# Power_supplies.net
KiCad netlist of a schematic drawn in Altium Designer
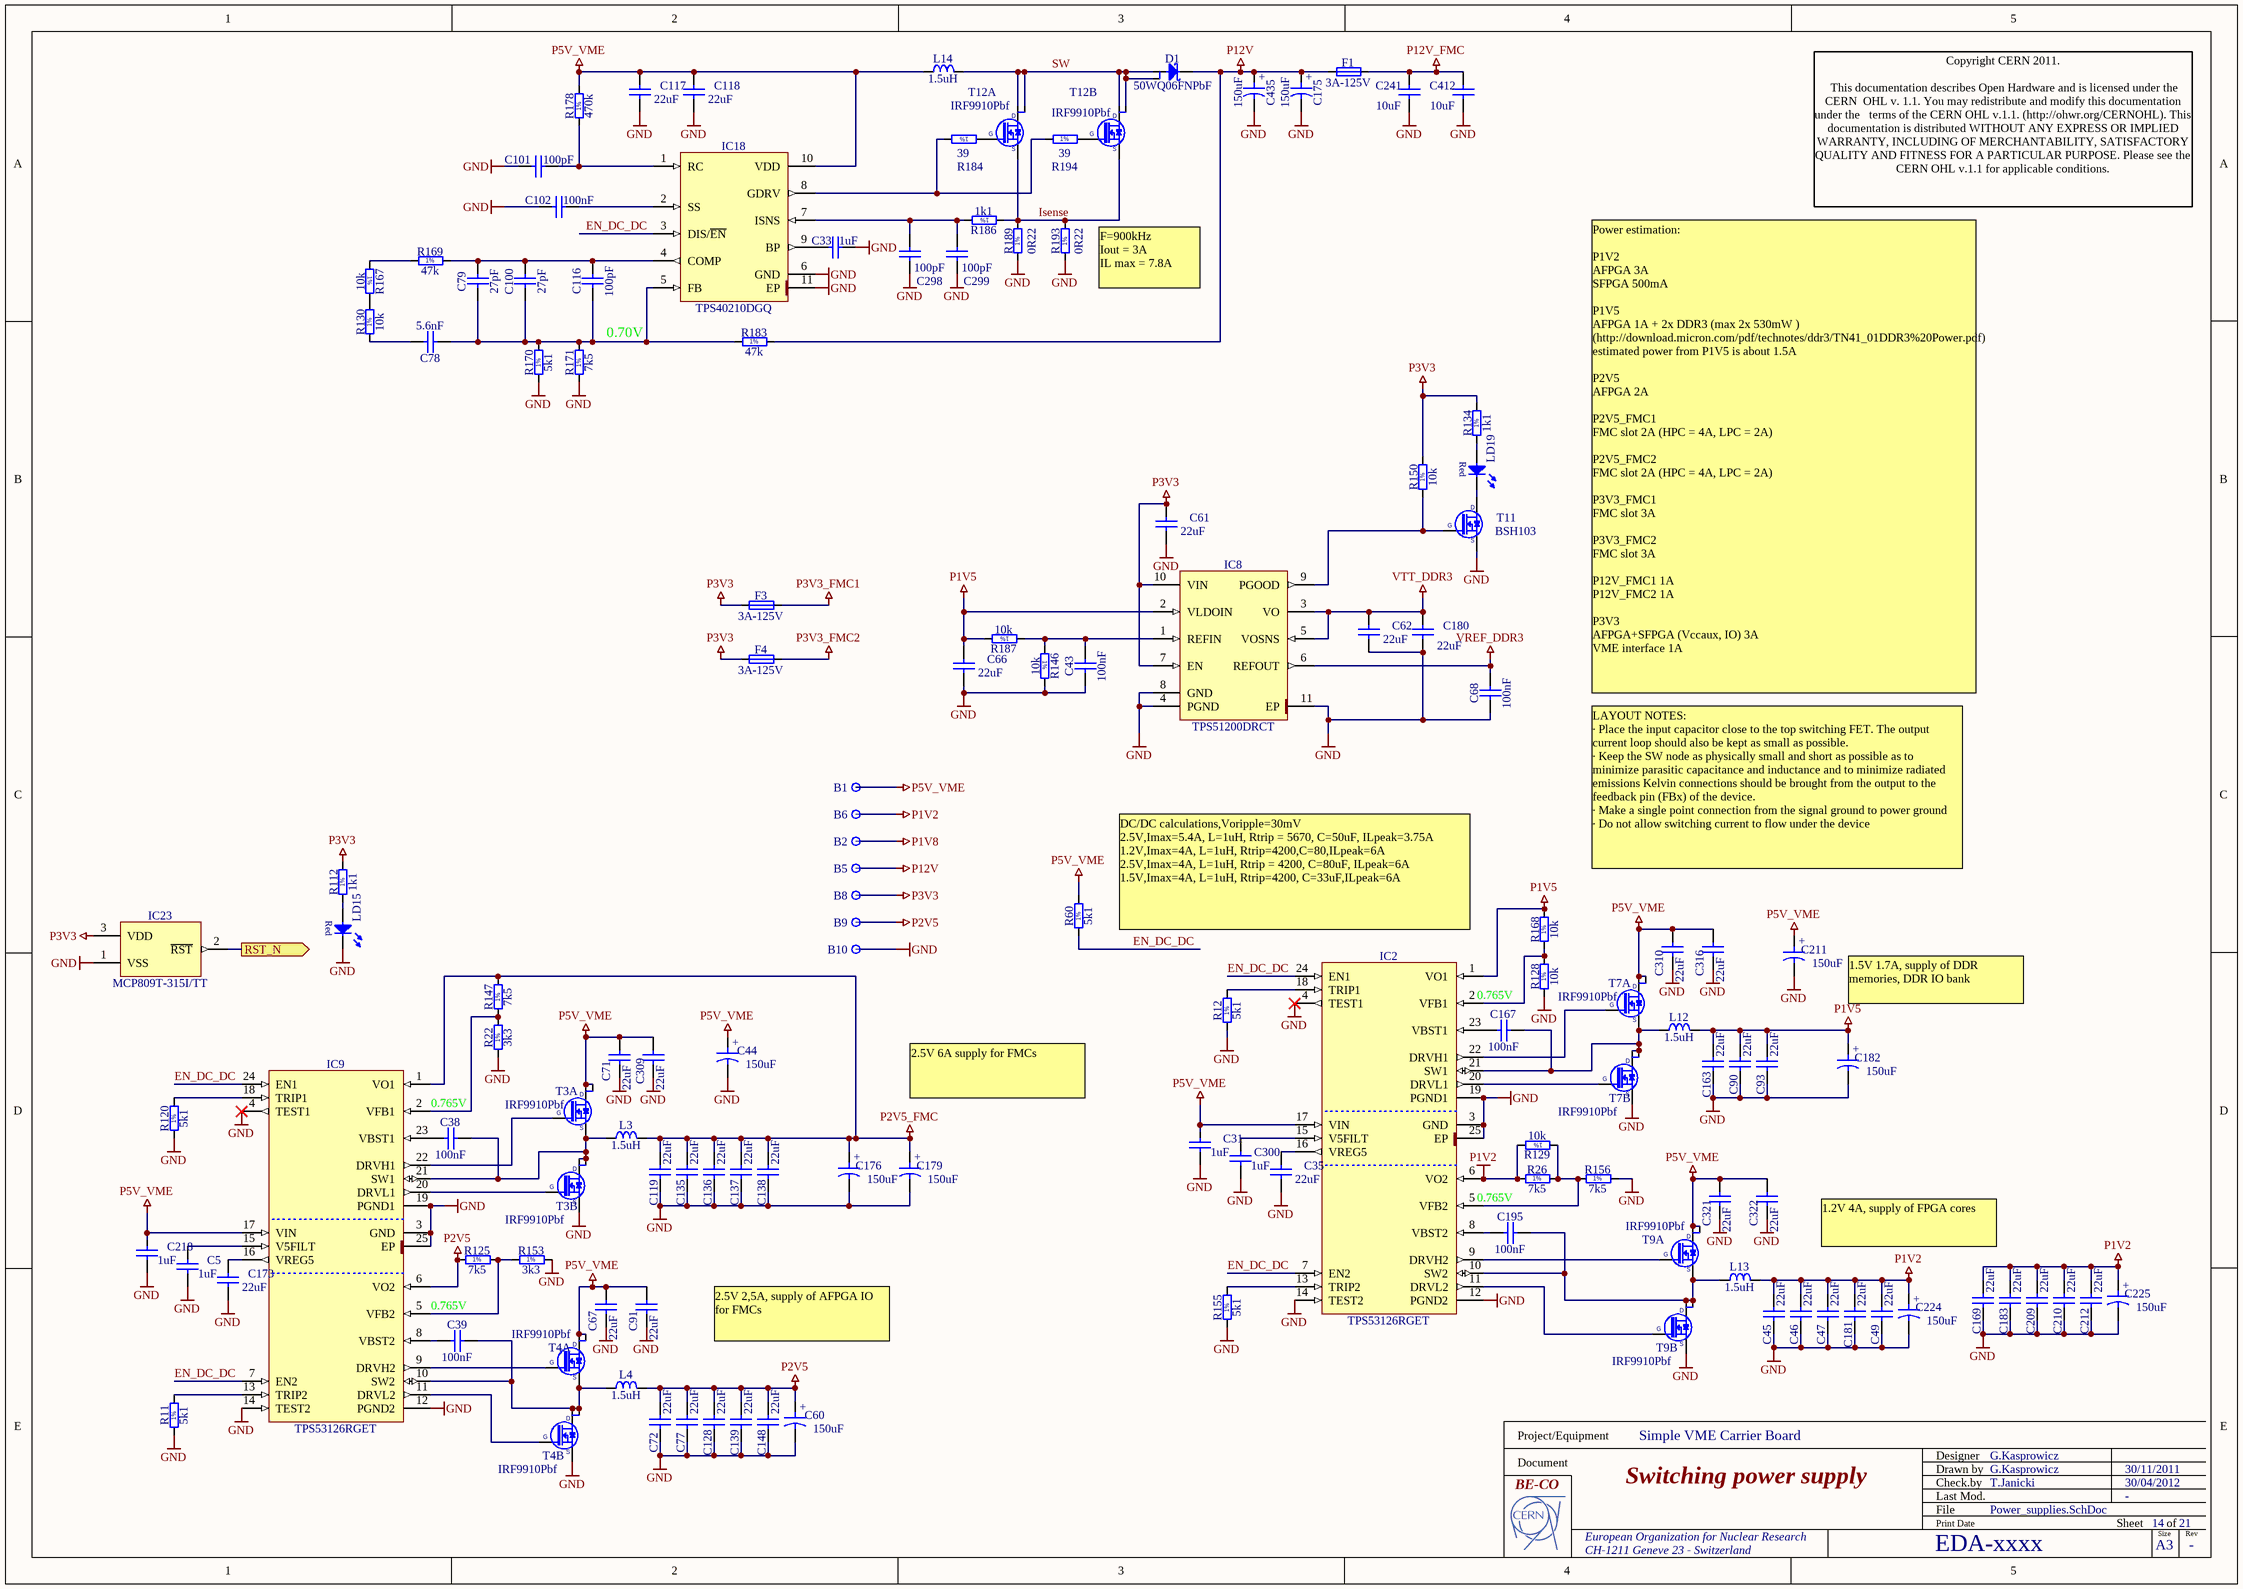
[diagram p0: Power_supplies.SchDoc]

(export (version "E")
  (design (tool "Eeschema 10.0.6"))
  (components
    (comp (ref "B1")
      (value "Plated Hole")
      (footprint "c130h80")
      (description "Single Terminal Socket")
      (fields (field (name "PART NUMBER") "PLATED_HOLE0.8_PAD1.3") (field (name "AUTHOR") "CERN DEM JLC"))
      (libsource (lib "Eletro-mechanical") (part "Single Terminal Socket"))
    )
    (comp (ref "B2")
      (value "Plated Hole")
      (footprint "c130h80")
      (description "Single Terminal Socket")
      (fields (field (name "PART NUMBER") "PLATED_HOLE0.8_PAD1.3") (field (name "AUTHOR") "CERN DEM JLC"))
      (libsource (lib "Eletro-mechanical") (part "Single Terminal Socket"))
    )
    (comp (ref "B5")
      (value "Plated Hole")
      (footprint "c130h80")
      (description "Single Terminal Socket")
      (fields (field (name "PART NUMBER") "PLATED_HOLE0.8_PAD1.3") (field (name "AUTHOR") "CERN DEM JLC"))
      (libsource (lib "Eletro-mechanical") (part "Single Terminal Socket"))
    )
    (comp (ref "B6")
      (value "Plated Hole")
      (footprint "c130h80")
      (description "Single Terminal Socket")
      (fields (field (name "PART NUMBER") "PLATED_HOLE0.8_PAD1.3") (field (name "AUTHOR") "CERN DEM JLC"))
      (libsource (lib "Eletro-mechanical") (part "Single Terminal Socket"))
    )
    (comp (ref "B8")
      (value "Plated Hole")
      (footprint "c130h80")
      (description "Single Terminal Socket")
      (fields (field (name "PART NUMBER") "PLATED_HOLE0.8_PAD1.3") (field (name "AUTHOR") "CERN DEM JLC"))
      (libsource (lib "Eletro-mechanical") (part "Single Terminal Socket"))
    )
    (comp (ref "B9")
      (value "Plated Hole")
      (footprint "c130h80")
      (description "Single Terminal Socket")
      (fields (field (name "PART NUMBER") "PLATED_HOLE0.8_PAD1.3") (field (name "AUTHOR") "CERN DEM JLC"))
      (libsource (lib "Eletro-mechanical") (part "Single Terminal Socket"))
    )
    (comp (ref "B10")
      (value "Plated Hole")
      (footprint "c130h80")
      (description "Single Terminal Socket")
      (fields (field (name "PART NUMBER") "PLATED_HOLE0.8_PAD1.3") (field (name "AUTHOR") "CERN DEM JLC"))
      (libsource (lib "Eletro-mechanical") (part "Single Terminal Socket"))
    )
    (comp (ref "C5")
      (value "1uF")
      (footprint "CAPC1608X87N")
      (description "Non-polarised capacitor")
      (fields
        (field (name "PART NUMBER") "CC0603_1UF_16V_10%_X7R")
        (field (name "VOLTAGE") "16V")
        (field (name "AUTHOR") "CERN DEM JLC")
      )
      (libsource (lib "Capacitors") (part "Capacitor - non polarized"))
    )
    (comp (ref "C31")
      (value "1uF")
      (footprint "CAPC1608X87N")
      (description "Non-polarised capacitor")
      (fields
        (field (name "PART NUMBER") "CC0603_1UF_16V_10%_X7R")
        (field (name "VOLTAGE") "16V")
        (field (name "AUTHOR") "CERN DEM JLC")
      )
      (libsource (lib "Capacitors") (part "Capacitor - non polarized"))
    )
    (comp (ref "C33")
      (value "1uF")
      (footprint "CAPC1608X87N")
      (description "Non-polarised capacitor")
      (fields
        (field (name "PART NUMBER") "CC0603_1UF_16V_10%_X7R")
        (field (name "VOLTAGE") "16V")
        (field (name "AUTHOR") "CERN DEM JLC")
      )
      (libsource (lib "Capacitors") (part "Capacitor - non polarized"))
    )
    (comp (ref "C35")
      (value "22uF")
      (footprint "CAPC3216X180N")
      (description "Non-polarised capacitor")
      (fields
        (field (name "PART NUMBER") "CC1206_22UF_10V_10%_X7R")
        (field (name "VOLTAGE") "10V")
        (field (name "AUTHOR") "CERN DEM JLC")
      )
      (libsource (lib "Capacitors") (part "Capacitor - non polarized"))
    )
    (comp (ref "C38")
      (value "100nF")
      (footprint "CAPC1005X55N")
      (description "Non-polarised capacitor")
      (fields
        (field (name "PART NUMBER") "CC0402_100NF_16V_10%_X7R")
        (field (name "VOLTAGE") "16V")
        (field (name "AUTHOR") "CERN DEM JLC")
      )
      (libsource (lib "Capacitors") (part "Capacitor - non polarized"))
    )
    (comp (ref "C39")
      (value "100nF")
      (footprint "CAPC1005X55N")
      (description "Non-polarised capacitor")
      (fields
        (field (name "PART NUMBER") "CC0402_100NF_16V_10%_X7R")
        (field (name "VOLTAGE") "16V")
        (field (name "AUTHOR") "CERN DEM JLC")
      )
      (libsource (lib "Capacitors") (part "Capacitor - non polarized"))
    )
    (comp (ref "C43")
      (value "100nF")
      (footprint "CAPC1005X55N")
      (description "Non-polarised capacitor")
      (fields
        (field (name "PART NUMBER") "CC0402_100NF_16V_10%_X7R")
        (field (name "VOLTAGE") "16V")
        (field (name "AUTHOR") "CERN DEM JLC")
      )
      (libsource (lib "Capacitors") (part "Capacitor - non polarized"))
    )
    (comp (ref "C44")
      (value "150uF")
      (footprint "CAPPR350-850X700")
      (description "Polarised capacitor")
      (fields
        (field (name "PART NUMBER") "CAER_150UF_6.3V_20%_SANYO_6SEQP150M")
        (field (name "VOLTAGE") "6.3V")
        (field (name "AUTHOR") "CERN DEM JLC")
      )
      (libsource (lib "Capacitors") (part "Capacitor - polarized"))
    )
    (comp (ref "C45")
      (value "22uF")
      (footprint "CAPC3216X180N")
      (description "Non-polarised capacitor")
      (fields
        (field (name "PART NUMBER") "CC1206_22UF_10V_10%_X7R")
        (field (name "VOLTAGE") "10V")
        (field (name "AUTHOR") "CERN DEM JLC")
      )
      (libsource (lib "Capacitors") (part "Capacitor - non polarized"))
    )
    (comp (ref "C46")
      (value "22uF")
      (footprint "CAPC3216X180N")
      (description "Non-polarised capacitor")
      (fields
        (field (name "PART NUMBER") "CC1206_22UF_10V_10%_X7R")
        (field (name "VOLTAGE") "10V")
        (field (name "AUTHOR") "CERN DEM JLC")
      )
      (libsource (lib "Capacitors") (part "Capacitor - non polarized"))
    )
    (comp (ref "C47")
      (value "22uF")
      (footprint "CAPC3216X180N")
      (description "Non-polarised capacitor")
      (fields
        (field (name "PART NUMBER") "CC1206_22UF_10V_10%_X7R")
        (field (name "VOLTAGE") "10V")
        (field (name "AUTHOR") "CERN DEM JLC")
      )
      (libsource (lib "Capacitors") (part "Capacitor - non polarized"))
    )
    (comp (ref "C49")
      (value "22uF")
      (footprint "CAPC3216X180N")
      (description "Non-polarised capacitor")
      (fields
        (field (name "PART NUMBER") "CC1206_22UF_10V_10%_X7R")
        (field (name "VOLTAGE") "10V")
        (field (name "AUTHOR") "CERN DEM JLC")
      )
      (libsource (lib "Capacitors") (part "Capacitor - non polarized"))
    )
    (comp (ref "C60")
      (value "150uF")
      (footprint "CAPPR350-850X700")
      (description "Polarised capacitor")
      (fields
        (field (name "PART NUMBER") "CAER_150UF_6.3V_20%_SANYO_6SEQP150M")
        (field (name "VOLTAGE") "6.3V")
        (field (name "AUTHOR") "CERN DEM JLC")
      )
      (libsource (lib "Capacitors") (part "Capacitor - polarized"))
    )
    (comp (ref "C61")
      (value "22uF")
      (footprint "CAPC3216X180N")
      (description "Non-polarised capacitor")
      (fields
        (field (name "PART NUMBER") "CC1206_22UF_10V_10%_X7R")
        (field (name "VOLTAGE") "10V")
        (field (name "AUTHOR") "CERN DEM JLC")
      )
      (libsource (lib "Capacitors") (part "Capacitor - non polarized"))
    )
    (comp (ref "C62")
      (value "22uF")
      (footprint "CAPC3216X180N")
      (description "Non-polarised capacitor")
      (fields
        (field (name "PART NUMBER") "CC1206_22UF_10V_10%_X7R")
        (field (name "VOLTAGE") "10V")
        (field (name "AUTHOR") "CERN DEM JLC")
      )
      (libsource (lib "Capacitors") (part "Capacitor - non polarized"))
    )
    (comp (ref "C66")
      (value "22uF")
      (footprint "CAPC3216X180N")
      (description "Non-polarised capacitor")
      (fields
        (field (name "PART NUMBER") "CC1206_22UF_10V_10%_X7R")
        (field (name "VOLTAGE") "10V")
        (field (name "AUTHOR") "CERN DEM JLC")
      )
      (libsource (lib "Capacitors") (part "Capacitor - non polarized"))
    )
    (comp (ref "C67")
      (value "22uF")
      (footprint "CAPC3216X180N")
      (description "Non-polarised capacitor")
      (fields
        (field (name "PART NUMBER") "CC1206_22UF_10V_10%_X7R")
        (field (name "VOLTAGE") "10V")
        (field (name "AUTHOR") "CERN DEM JLC")
      )
      (libsource (lib "Capacitors") (part "Capacitor - non polarized"))
    )
    (comp (ref "C68")
      (value "100nF")
      (footprint "CAPC1005X55N")
      (description "Non-polarised capacitor")
      (fields
        (field (name "PART NUMBER") "CC0402_100NF_16V_10%_X7R")
        (field (name "VOLTAGE") "16V")
        (field (name "AUTHOR") "CERN DEM JLC")
      )
      (libsource (lib "Capacitors") (part "Capacitor - non polarized"))
    )
    (comp (ref "C71")
      (value "22uF")
      (footprint "CAPC3216X180N")
      (description "Non-polarised capacitor")
      (fields
        (field (name "PART NUMBER") "CC1206_22UF_10V_10%_X7R")
        (field (name "VOLTAGE") "10V")
        (field (name "AUTHOR") "CERN DEM JLC")
      )
      (libsource (lib "Capacitors") (part "Capacitor - non polarized"))
    )
    (comp (ref "C72")
      (value "22uF")
      (footprint "CAPC3216X180N")
      (description "Non-polarised capacitor")
      (fields
        (field (name "PART NUMBER") "CC1206_22UF_10V_10%_X7R")
        (field (name "VOLTAGE") "10V")
        (field (name "AUTHOR") "CERN DEM JLC")
      )
      (libsource (lib "Capacitors") (part "Capacitor - non polarized"))
    )
    (comp (ref "C77")
      (value "22uF")
      (footprint "CAPC3216X180N")
      (description "Non-polarised capacitor")
      (fields
        (field (name "PART NUMBER") "CC1206_22UF_10V_10%_X7R")
        (field (name "VOLTAGE") "10V")
        (field (name "AUTHOR") "CERN DEM JLC")
      )
      (libsource (lib "Capacitors") (part "Capacitor - non polarized"))
    )
    (comp (ref "C78")
      (value "5.6nF")
      (footprint "CAPC1608X87N")
      (description "Non-polarised capacitor")
      (fields
        (field (name "PART NUMBER") "CC0603_5.6NF_50V_5%_X7R")
        (field (name "VOLTAGE") "50V")
        (field (name "AUTHOR") "CERN DEM JLC")
      )
      (libsource (lib "Capacitors") (part "Capacitor - non polarized"))
    )
    (comp (ref "C79")
      (value "27pF")
      (footprint "CAPC1608X87N")
      (description "Non-polarised capacitor")
      (fields
        (field (name "PART NUMBER") "CC0603_27PF_50V_5%_NP0")
        (field (name "VOLTAGE") "50V")
        (field (name "AUTHOR") "CERN DEM JLC")
      )
      (libsource (lib "Capacitors") (part "Capacitor - non polarized"))
    )
    (comp (ref "C90")
      (value "22uF")
      (footprint "CAPC3216X180N")
      (description "Non-polarised capacitor")
      (fields
        (field (name "PART NUMBER") "CC1206_22UF_10V_10%_X7R")
        (field (name "VOLTAGE") "10V")
        (field (name "AUTHOR") "CERN DEM JLC")
      )
      (libsource (lib "Capacitors") (part "Capacitor - non polarized"))
    )
    (comp (ref "C91")
      (value "22uF")
      (footprint "CAPC3216X180N")
      (description "Non-polarised capacitor")
      (fields
        (field (name "PART NUMBER") "CC1206_22UF_10V_10%_X7R")
        (field (name "VOLTAGE") "10V")
        (field (name "AUTHOR") "CERN DEM JLC")
      )
      (libsource (lib "Capacitors") (part "Capacitor - non polarized"))
    )
    (comp (ref "C93")
      (value "22uF")
      (footprint "CAPC3216X180N")
      (description "Non-polarised capacitor")
      (fields
        (field (name "PART NUMBER") "CC1206_22UF_10V_10%_X7R")
        (field (name "VOLTAGE") "10V")
        (field (name "AUTHOR") "CERN DEM JLC")
      )
      (libsource (lib "Capacitors") (part "Capacitor - non polarized"))
    )
    (comp (ref "C100")
      (value "27pF")
      (footprint "CAPC1608X87N")
      (description "Non-polarised capacitor")
      (fields
        (field (name "PART NUMBER") "CC0603_27PF_50V_5%_NP0")
        (field (name "VOLTAGE") "50V")
        (field (name "AUTHOR") "CERN DEM JLC")
      )
      (libsource (lib "Capacitors") (part "Capacitor - non polarized"))
    )
    (comp (ref "C101")
      (value "100pF")
      (footprint "CAPC1608X87N")
      (description "Non-polarised capacitor")
      (fields
        (field (name "PART NUMBER") "CC0603_100PF_50V_5%_NP0")
        (field (name "VOLTAGE") "50V")
        (field (name "AUTHOR") "CERN DEM JLC")
      )
      (libsource (lib "Capacitors") (part "Capacitor - non polarized"))
    )
    (comp (ref "C102")
      (value "100nF")
      (footprint "CAPC1005X55N")
      (description "Non-polarised capacitor")
      (fields
        (field (name "PART NUMBER") "CC0402_100NF_16V_10%_X7R")
        (field (name "VOLTAGE") "16V")
        (field (name "AUTHOR") "CERN DEM JLC")
      )
      (libsource (lib "Capacitors") (part "Capacitor - non polarized"))
    )
    (comp (ref "C116")
      (value "100pF")
      (footprint "CAPC1608X87N")
      (description "Non-polarised capacitor")
      (fields
        (field (name "PART NUMBER") "CC0603_100PF_50V_5%_NP0")
        (field (name "VOLTAGE") "50V")
        (field (name "AUTHOR") "CERN DEM JLC")
      )
      (libsource (lib "Capacitors") (part "Capacitor - non polarized"))
    )
    (comp (ref "C117")
      (value "22uF")
      (footprint "CAPC3216X180N")
      (description "Non-polarised capacitor")
      (fields
        (field (name "PART NUMBER") "CC1206_22UF_10V_10%_X7R")
        (field (name "VOLTAGE") "10V")
        (field (name "AUTHOR") "CERN DEM JLC")
      )
      (libsource (lib "Capacitors") (part "Capacitor - non polarized"))
    )
    (comp (ref "C118")
      (value "22uF")
      (footprint "CAPC3216X180N")
      (description "Non-polarised capacitor")
      (fields
        (field (name "PART NUMBER") "CC1206_22UF_10V_10%_X7R")
        (field (name "VOLTAGE") "10V")
        (field (name "AUTHOR") "CERN DEM JLC")
      )
      (libsource (lib "Capacitors") (part "Capacitor - non polarized"))
    )
    (comp (ref "C119")
      (value "22uF")
      (footprint "CAPC3216X180N")
      (description "Non-polarised capacitor")
      (fields
        (field (name "PART NUMBER") "CC1206_22UF_10V_10%_X7R")
        (field (name "VOLTAGE") "10V")
        (field (name "AUTHOR") "CERN DEM JLC")
      )
      (libsource (lib "Capacitors") (part "Capacitor - non polarized"))
    )
    (comp (ref "C128")
      (value "22uF")
      (footprint "CAPC3216X180N")
      (description "Non-polarised capacitor")
      (fields
        (field (name "PART NUMBER") "CC1206_22UF_10V_10%_X7R")
        (field (name "VOLTAGE") "10V")
        (field (name "AUTHOR") "CERN DEM JLC")
      )
      (libsource (lib "Capacitors") (part "Capacitor - non polarized"))
    )
    (comp (ref "C135")
      (value "22uF")
      (footprint "CAPC3216X180N")
      (description "Non-polarised capacitor")
      (fields
        (field (name "PART NUMBER") "CC1206_22UF_10V_10%_X7R")
        (field (name "VOLTAGE") "10V")
        (field (name "AUTHOR") "CERN DEM JLC")
      )
      (libsource (lib "Capacitors") (part "Capacitor - non polarized"))
    )
    (comp (ref "C136")
      (value "22uF")
      (footprint "CAPC3216X180N")
      (description "Non-polarised capacitor")
      (fields
        (field (name "PART NUMBER") "CC1206_22UF_10V_10%_X7R")
        (field (name "VOLTAGE") "10V")
        (field (name "AUTHOR") "CERN DEM JLC")
      )
      (libsource (lib "Capacitors") (part "Capacitor - non polarized"))
    )
    (comp (ref "C137")
      (value "22uF")
      (footprint "CAPC3216X180N")
      (description "Non-polarised capacitor")
      (fields
        (field (name "PART NUMBER") "CC1206_22UF_10V_10%_X7R")
        (field (name "VOLTAGE") "10V")
        (field (name "AUTHOR") "CERN DEM JLC")
      )
      (libsource (lib "Capacitors") (part "Capacitor - non polarized"))
    )
    (comp (ref "C138")
      (value "22uF")
      (footprint "CAPC3216X180N")
      (description "Non-polarised capacitor")
      (fields
        (field (name "PART NUMBER") "CC1206_22UF_10V_10%_X7R")
        (field (name "VOLTAGE") "10V")
        (field (name "AUTHOR") "CERN DEM JLC")
      )
      (libsource (lib "Capacitors") (part "Capacitor - non polarized"))
    )
    (comp (ref "C139")
      (value "22uF")
      (footprint "CAPC3216X180N")
      (description "Non-polarised capacitor")
      (fields
        (field (name "PART NUMBER") "CC1206_22UF_10V_10%_X7R")
        (field (name "VOLTAGE") "10V")
        (field (name "AUTHOR") "CERN DEM JLC")
      )
      (libsource (lib "Capacitors") (part "Capacitor - non polarized"))
    )
    (comp (ref "C148")
      (value "22uF")
      (footprint "CAPC3216X180N")
      (description "Non-polarised capacitor")
      (fields
        (field (name "PART NUMBER") "CC1206_22UF_10V_10%_X7R")
        (field (name "VOLTAGE") "10V")
        (field (name "AUTHOR") "CERN DEM JLC")
      )
      (libsource (lib "Capacitors") (part "Capacitor - non polarized"))
    )
    (comp (ref "C163")
      (value "22uF")
      (footprint "CAPC3216X180N")
      (description "Non-polarised capacitor")
      (fields
        (field (name "PART NUMBER") "CC1206_22UF_10V_10%_X7R")
        (field (name "VOLTAGE") "10V")
        (field (name "AUTHOR") "CERN DEM JLC")
      )
      (libsource (lib "Capacitors") (part "Capacitor - non polarized"))
    )
    (comp (ref "C167")
      (value "100nF")
      (footprint "CAPC1005X55N")
      (description "Non-polarised capacitor")
      (fields
        (field (name "PART NUMBER") "CC0402_100NF_16V_10%_X7R")
        (field (name "VOLTAGE") "16V")
        (field (name "AUTHOR") "CERN DEM JLC")
      )
      (libsource (lib "Capacitors") (part "Capacitor - non polarized"))
    )
    (comp (ref "C169")
      (value "22uF")
      (footprint "CAPC3216X180N")
      (description "Non-polarised capacitor")
      (fields
        (field (name "PART NUMBER") "CC1206_22UF_10V_10%_X7R")
        (field (name "VOLTAGE") "10V")
        (field (name "AUTHOR") "CERN DEM JLC")
      )
      (libsource (lib "Capacitors") (part "Capacitor - non polarized"))
    )
    (comp (ref "C173")
      (value "22uF")
      (footprint "CAPC3216X180N")
      (description "Non-polarised capacitor")
      (fields
        (field (name "PART NUMBER") "CC1206_22UF_10V_10%_X7R")
        (field (name "VOLTAGE") "10V")
        (field (name "AUTHOR") "CERN DEM JLC")
      )
      (libsource (lib "Capacitors") (part "Capacitor - non polarized"))
    )
    (comp (ref "C175")
      (value "150uF")
      (footprint "CAPPR500-1050X800")
      (description "Polarised capacitor")
      (fields
        (field (name "PART NUMBER") "CAER_150UF_16V_20%_SANYO_16SEQP150M")
        (field (name "VOLTAGE") "16V")
        (field (name "AUTHOR") "CERN DEM JLC")
      )
      (libsource (lib "Capacitors") (part "Capacitor - polarized"))
    )
    (comp (ref "C176")
      (value "150uF")
      (footprint "CAPPR350-850X700")
      (description "Polarised capacitor")
      (fields
        (field (name "PART NUMBER") "CAER_150UF_6.3V_20%_SANYO_6SEQP150M")
        (field (name "VOLTAGE") "6.3V")
        (field (name "AUTHOR") "CERN DEM JLC")
      )
      (libsource (lib "Capacitors") (part "Capacitor - polarized"))
    )
    (comp (ref "C179")
      (value "150uF")
      (footprint "CAPPR350-850X700")
      (description "Polarised capacitor")
      (fields
        (field (name "PART NUMBER") "CAER_150UF_6.3V_20%_SANYO_6SEQP150M")
        (field (name "VOLTAGE") "6.3V")
        (field (name "AUTHOR") "CERN DEM JLC")
      )
      (libsource (lib "Capacitors") (part "Capacitor - polarized"))
    )
    (comp (ref "C180")
      (value "22uF")
      (footprint "CAPC3216X180N")
      (description "Non-polarised capacitor")
      (fields
        (field (name "PART NUMBER") "CC1206_22UF_10V_10%_X7R")
        (field (name "VOLTAGE") "10V")
        (field (name "AUTHOR") "CERN DEM JLC")
      )
      (libsource (lib "Capacitors") (part "Capacitor - non polarized"))
    )
    (comp (ref "C181")
      (value "22uF")
      (footprint "CAPC3216X180N")
      (description "Non-polarised capacitor")
      (fields
        (field (name "PART NUMBER") "CC1206_22UF_10V_10%_X7R")
        (field (name "VOLTAGE") "10V")
        (field (name "AUTHOR") "CERN DEM JLC")
      )
      (libsource (lib "Capacitors") (part "Capacitor - non polarized"))
    )
    (comp (ref "C182")
      (value "150uF")
      (footprint "CAPPR350-850X700")
      (description "Polarised capacitor")
      (fields
        (field (name "PART NUMBER") "CAER_150UF_6.3V_20%_SANYO_6SEQP150M")
        (field (name "VOLTAGE") "6.3V")
        (field (name "AUTHOR") "CERN DEM JLC")
      )
      (libsource (lib "Capacitors") (part "Capacitor - polarized"))
    )
    (comp (ref "C183")
      (value "22uF")
      (footprint "CAPC3216X180N")
      (description "Non-polarised capacitor")
      (fields
        (field (name "PART NUMBER") "CC1206_22UF_10V_10%_X7R")
        (field (name "VOLTAGE") "10V")
        (field (name "AUTHOR") "CERN DEM JLC")
      )
      (libsource (lib "Capacitors") (part "Capacitor - non polarized"))
    )
    (comp (ref "C195")
      (value "100nF")
      (footprint "CAPC1005X55N")
      (description "Non-polarised capacitor")
      (fields
        (field (name "PART NUMBER") "CC0402_100NF_16V_10%_X7R")
        (field (name "VOLTAGE") "16V")
        (field (name "AUTHOR") "CERN DEM JLC")
      )
      (libsource (lib "Capacitors") (part "Capacitor - non polarized"))
    )
    (comp (ref "C209")
      (value "22uF")
      (footprint "CAPC3216X180N")
      (description "Non-polarised capacitor")
      (fields
        (field (name "PART NUMBER") "CC1206_22UF_10V_10%_X7R")
        (field (name "VOLTAGE") "10V")
        (field (name "AUTHOR") "CERN DEM JLC")
      )
      (libsource (lib "Capacitors") (part "Capacitor - non polarized"))
    )
    (comp (ref "C210")
      (value "22uF")
      (footprint "CAPC3216X180N")
      (description "Non-polarised capacitor")
      (fields
        (field (name "PART NUMBER") "CC1206_22UF_10V_10%_X7R")
        (field (name "VOLTAGE") "10V")
        (field (name "AUTHOR") "CERN DEM JLC")
      )
      (libsource (lib "Capacitors") (part "Capacitor - non polarized"))
    )
    (comp (ref "C211")
      (value "150uF")
      (footprint "CAPPR350-850X700")
      (description "Polarised capacitor")
      (fields
        (field (name "PART NUMBER") "CAER_150UF_6.3V_20%_SANYO_6SEQP150M")
        (field (name "VOLTAGE") "6.3V")
        (field (name "AUTHOR") "CERN DEM JLC")
      )
      (libsource (lib "Capacitors") (part "Capacitor - polarized"))
    )
    (comp (ref "C212")
      (value "22uF")
      (footprint "CAPC3216X180N")
      (description "Non-polarised capacitor")
      (fields
        (field (name "PART NUMBER") "CC1206_22UF_10V_10%_X7R")
        (field (name "VOLTAGE") "10V")
        (field (name "AUTHOR") "CERN DEM JLC")
      )
      (libsource (lib "Capacitors") (part "Capacitor - non polarized"))
    )
    (comp (ref "C218")
      (value "1uF")
      (footprint "CAPC1608X87N")
      (description "Non-polarised capacitor")
      (fields
        (field (name "PART NUMBER") "CC0603_1UF_16V_10%_X7R")
        (field (name "VOLTAGE") "16V")
        (field (name "AUTHOR") "CERN DEM JLC")
      )
      (libsource (lib "Capacitors") (part "Capacitor - non polarized"))
    )
    (comp (ref "C224")
      (value "150uF")
      (footprint "CAPPR350-850X700")
      (description "Polarised capacitor")
      (fields
        (field (name "PART NUMBER") "CAER_150UF_6.3V_20%_SANYO_6SEQP150M")
        (field (name "VOLTAGE") "6.3V")
        (field (name "AUTHOR") "CERN DEM JLC")
      )
      (libsource (lib "Capacitors") (part "Capacitor - polarized"))
    )
    (comp (ref "C225")
      (value "150uF")
      (footprint "CAPPR350-850X700")
      (description "Polarised capacitor")
      (fields
        (field (name "PART NUMBER") "CAER_150UF_6.3V_20%_SANYO_6SEQP150M")
        (field (name "VOLTAGE") "6.3V")
        (field (name "AUTHOR") "CERN DEM JLC")
      )
      (libsource (lib "Capacitors") (part "Capacitor - polarized"))
    )
    (comp (ref "C241")
      (value "10uF")
      (footprint "CAPC3225X270N")
      (description "Non-polarised capacitor")
      (fields
        (field (name "PART NUMBER") "CC1210_10UF_25V_10%_X7R")
        (field (name "VOLTAGE") "25V")
        (field (name "AUTHOR") "CERN DEM JLC")
      )
      (libsource (lib "Capacitors") (part "Capacitor - non polarized"))
    )
    (comp (ref "C298")
      (value "100pF")
      (footprint "CAPC1608X87N")
      (description "Non-polarised capacitor")
      (fields
        (field (name "PART NUMBER") "CC0603_100PF_50V_5%_NP0")
        (field (name "VOLTAGE") "50V")
        (field (name "AUTHOR") "CERN DEM JLC")
      )
      (libsource (lib "Capacitors") (part "Capacitor - non polarized"))
    )
    (comp (ref "C299")
      (value "100pF")
      (footprint "CAPC1608X87N")
      (description "Non-polarised capacitor")
      (fields
        (field (name "PART NUMBER") "CC0603_100PF_50V_5%_NP0")
        (field (name "VOLTAGE") "50V")
        (field (name "AUTHOR") "CERN DEM JLC")
      )
      (libsource (lib "Capacitors") (part "Capacitor - non polarized"))
    )
    (comp (ref "C300")
      (value "1uF")
      (footprint "CAPC1608X87N")
      (description "Non-polarised capacitor")
      (fields
        (field (name "PART NUMBER") "CC0603_1UF_16V_10%_X7R")
        (field (name "VOLTAGE") "16V")
        (field (name "AUTHOR") "CERN DEM JLC")
      )
      (libsource (lib "Capacitors") (part "Capacitor - non polarized"))
    )
    (comp (ref "C309")
      (value "22uF")
      (footprint "CAPC3216X180N")
      (description "Non-polarised capacitor")
      (fields
        (field (name "PART NUMBER") "CC1206_22UF_10V_10%_X7R")
        (field (name "VOLTAGE") "10V")
        (field (name "AUTHOR") "CERN DEM JLC")
      )
      (libsource (lib "Capacitors") (part "Capacitor - non polarized"))
    )
    (comp (ref "C310")
      (value "22uF")
      (footprint "CAPC3216X180N")
      (description "Non-polarised capacitor")
      (fields
        (field (name "PART NUMBER") "CC1206_22UF_10V_10%_X7R")
        (field (name "VOLTAGE") "10V")
        (field (name "AUTHOR") "CERN DEM JLC")
      )
      (libsource (lib "Capacitors") (part "Capacitor - non polarized"))
    )
    (comp (ref "C316")
      (value "22uF")
      (footprint "CAPC3216X180N")
      (description "Non-polarised capacitor")
      (fields
        (field (name "PART NUMBER") "CC1206_22UF_10V_10%_X7R")
        (field (name "VOLTAGE") "10V")
        (field (name "AUTHOR") "CERN DEM JLC")
      )
      (libsource (lib "Capacitors") (part "Capacitor - non polarized"))
    )
    (comp (ref "C321")
      (value "22uF")
      (footprint "CAPC3216X180N")
      (description "Non-polarised capacitor")
      (fields
        (field (name "PART NUMBER") "CC1206_22UF_10V_10%_X7R")
        (field (name "VOLTAGE") "10V")
        (field (name "AUTHOR") "CERN DEM JLC")
      )
      (libsource (lib "Capacitors") (part "Capacitor - non polarized"))
    )
    (comp (ref "C322")
      (value "22uF")
      (footprint "CAPC3216X180N")
      (description "Non-polarised capacitor")
      (fields
        (field (name "PART NUMBER") "CC1206_22UF_10V_10%_X7R")
        (field (name "VOLTAGE") "10V")
        (field (name "AUTHOR") "CERN DEM JLC")
      )
      (libsource (lib "Capacitors") (part "Capacitor - non polarized"))
    )
    (comp (ref "C412")
      (value "10uF")
      (footprint "CAPC3225X270N")
      (description "Non-polarised capacitor")
      (fields
        (field (name "PART NUMBER") "CC1210_10UF_25V_10%_X7R")
        (field (name "VOLTAGE") "25V")
        (field (name "AUTHOR") "CERN DEM JLC")
      )
      (libsource (lib "Capacitors") (part "Capacitor - non polarized"))
    )
    (comp (ref "C435")
      (value "150uF")
      (footprint "CAPPR500-1050X800")
      (description "Polarised capacitor")
      (fields
        (field (name "PART NUMBER") "CAER_150UF_16V_20%_SANYO_16SEQP150M")
        (field (name "VOLTAGE") "16V")
        (field (name "AUTHOR") "CERN DEM JLC")
      )
      (libsource (lib "Capacitors") (part "Capacitor - polarized"))
    )
    (comp (ref "D1")
      (value "50WQ06FNPbF")
      (footprint "TO228P991X239-3N-R546X521")
      (description "Diode  Schottky Anode pin 1 and 2 cathode pin 3")
      (fields
        (field (name "VOLTAGE") "60V")
        (field (name "POWER") "5.5A")
        (field (name "AUTHOR") "CERN DEM JLC")
      )
      (libsource (lib "ICs And Semiconductors") (part "Diode Schottky A1A2_C3"))
    )
    (comp (ref "F1")
      (value "3A-125V")
      (footprint "FUSE_LITTELFUSE_0154")
      (description "Fuse")
      (fields
        (field (name "PART NUMBER") "FUSE_LITTELFUSE_0154003.DR")
        (field (name "MANUFACTURER") "LITTELFUSE")
        (field (name "AUTHOR") "CERN DEM JMW")
      )
      (libsource (lib "Eletro-mechanical") (part "Fuse"))
    )
    (comp (ref "F3")
      (value "3A-125V")
      (footprint "FUSE_LITTELFUSE_0154")
      (description "Fuse")
      (fields
        (field (name "PART NUMBER") "FUSE_LITTELFUSE_0154003.DR")
        (field (name "MANUFACTURER") "LITTELFUSE")
        (field (name "AUTHOR") "CERN DEM JMW")
      )
      (libsource (lib "Eletro-mechanical") (part "Fuse"))
    )
    (comp (ref "F4")
      (value "3A-125V")
      (footprint "FUSE_LITTELFUSE_0154")
      (description "Fuse")
      (fields
        (field (name "PART NUMBER") "FUSE_LITTELFUSE_0154003.DR")
        (field (name "MANUFACTURER") "LITTELFUSE")
        (field (name "AUTHOR") "CERN DEM JMW")
      )
      (libsource (lib "Eletro-mechanical") (part "Fuse"))
    )
    (comp (ref "IC2")
      (value "TPS53126RGET")
      (footprint "QFN50P400X400X100-25N-S255")
      (description "Dual Synchronous Step-Down Controller For Low Voltage Power Rails")
      (fields (field (name "MANUFACTURER") "TEXAS INSTRUMENTS") (field (name "AUTHOR") "CERN DEM JLC"))
      (libsource (lib "ICs And Semiconductors") (part "TPS53126RGET"))
    )
    (comp (ref "IC8")
      (value "TPS51200DRCT")
      (footprint "SON50P300X300X100-11N-R175X250")
      (description "Sink/Source DDR Termination Regulator")
      (fields (field (name "MANUFACTURER") "TEXAS INSTRUMENTS") (field (name "AUTHOR") "CERN DEM JLC"))
      (libsource (lib "ICs And Semiconductors") (part "TPS51200DRC"))
    )
    (comp (ref "IC9")
      (value "TPS53126RGET")
      (footprint "QFN50P400X400X100-25N-S255")
      (description "Dual Synchronous Step-Down Controller For Low Voltage Power Rails")
      (fields (field (name "MANUFACTURER") "TEXAS INSTRUMENTS") (field (name "AUTHOR") "CERN DEM JLC"))
      (libsource (lib "ICs And Semiconductors") (part "TPS53126RGET"))
    )
    (comp (ref "IC18")
      (value "TPS40210DGQ")
      (footprint "SOP50P490X110-11N-R157X188")
      (description "4.5V To 52v Input Current Mode Boost Controller")
      (fields (field (name "MANUFACTURER") "TEXAS INSTRUMENTS") (field (name "AUTHOR") "CERN DEM JLC"))
      (libsource (lib "ICs And Semiconductors") (part "TPS40210DGQ"))
    )
    (comp (ref "IC23")
      (value "MCP809T-315I/TT")
      (footprint "SOT95P237X112-3N")
      (description "3.075V Microcontroller Supervisory Circuit With Push-Pull Output")
      (fields (field (name "MANUFACTURER") "MICROCHIP TECHNOLOGY") (field (name "AUTHOR") "CERN DEM JLC"))
      (libsource (lib "ICs And Semiconductors") (part "MCP809"))
    )
    (comp (ref "L3")
      (value "1.5uH")
      (footprint "IND_BOURNS_SRR1260")
      (description "Inductor")
      (fields
        (field (name "PART NUMBER") "IND_1.5UH_30%_BOURNS_SRR1260")
        (field (name "POWER") "8.8A")
        (field (name "AUTHOR") "CERN DEM JLC")
      )
      (libsource (lib "Inductors & Transformers") (part "Inductor"))
    )
    (comp (ref "L4")
      (value "1.5uH")
      (footprint "IND_BOURNS_SRR1260")
      (description "Inductor")
      (fields
        (field (name "PART NUMBER") "IND_1.5UH_30%_BOURNS_SRR1260")
        (field (name "POWER") "8.8A")
        (field (name "AUTHOR") "CERN DEM JLC")
      )
      (libsource (lib "Inductors & Transformers") (part "Inductor"))
    )
    (comp (ref "L12")
      (value "1.5uH")
      (footprint "IND_BOURNS_SRR1260")
      (description "Inductor")
      (fields
        (field (name "PART NUMBER") "IND_1.5UH_30%_BOURNS_SRR1260")
        (field (name "POWER") "8.8A")
        (field (name "AUTHOR") "CERN DEM JLC")
      )
      (libsource (lib "Inductors & Transformers") (part "Inductor"))
    )
    (comp (ref "L13")
      (value "1.5uH")
      (footprint "IND_BOURNS_SRR1260")
      (description "Inductor")
      (fields
        (field (name "PART NUMBER") "IND_1.5UH_30%_BOURNS_SRR1260")
        (field (name "POWER") "8.8A")
        (field (name "AUTHOR") "CERN DEM JLC")
      )
      (libsource (lib "Inductors & Transformers") (part "Inductor"))
    )
    (comp (ref "L14")
      (value "1.5uH")
      (footprint "IND_BOURNS_SRR1260")
      (description "Inductor")
      (fields
        (field (name "PART NUMBER") "IND_1.5UH_30%_BOURNS_SRR1260")
        (field (name "POWER") "8.8A")
        (field (name "AUTHOR") "CERN DEM JLC")
      )
      (libsource (lib "Inductors & Transformers") (part "Inductor"))
    )
    (comp (ref "LD15")
      (value "Red")
      (footprint "LEDC1608X80N_RED")
      (description "LED Red 1C 2A")
      (fields
        (field (name "PART NUMBER") "LED_ROHM_SML-311UTT86K")
        (field (name "MANUFACTURER") "ROHM")
        (field (name "AUTHOR") "CERN DEM JLC")
      )
      (libsource (lib "ICs And Semiconductors") (part "LED Red 1C 2A"))
    )
    (comp (ref "LD19")
      (value "Red")
      (footprint "LEDC1608X80N_RED")
      (description "LED Red 1C 2A")
      (fields
        (field (name "PART NUMBER") "LED_ROHM_SML-311UTT86K")
        (field (name "MANUFACTURER") "ROHM")
        (field (name "AUTHOR") "CERN DEM JLC")
      )
      (libsource (lib "ICs And Semiconductors") (part "LED Red 1C 2A"))
    )
    (comp (ref "R11")
      (value "5k1")
      (footprint "RESC1608X55N")
      (description "Resistor - 1%")
      (fields
        (field (name "PART NUMBER") "R0603_5K1_1%_0.1W_100PPM")
        (field (name "POWER") "0.1W")
        (field (name "AUTHOR") "CERN DEM JLC")
      )
      (libsource (lib "Resistors") (part "Resistor - 1%"))
    )
    (comp (ref "R12")
      (value "5k1")
      (footprint "RESC1608X55N")
      (description "Resistor - 1%")
      (fields
        (field (name "PART NUMBER") "R0603_5K1_1%_0.1W_100PPM")
        (field (name "POWER") "0.1W")
        (field (name "AUTHOR") "CERN DEM JLC")
      )
      (libsource (lib "Resistors") (part "Resistor - 1%"))
    )
    (comp (ref "R22")
      (value "3k3")
      (footprint "RESC1608X55N")
      (description "Resistor - 1%")
      (fields
        (field (name "PART NUMBER") "R0603_3K3_1%_0.1W_100PPM")
        (field (name "POWER") "0.1W")
        (field (name "AUTHOR") "CERN DEM JLC")
      )
      (libsource (lib "Resistors") (part "Resistor - 1%"))
    )
    (comp (ref "R26")
      (value "7k5")
      (footprint "RESC1608X55N")
      (description "Resistor - 1%")
      (fields
        (field (name "PART NUMBER") "R0603_7K5_1%_0.1W_100PPM")
        (field (name "POWER") "0.1W")
        (field (name "AUTHOR") "CERN DEM JLC")
      )
      (libsource (lib "Resistors") (part "Resistor - 1%"))
    )
    (comp (ref "R60")
      (value "5k1")
      (footprint "RESC1608X55N")
      (description "Resistor - 1%")
      (fields
        (field (name "PART NUMBER") "R0603_5K1_1%_0.1W_100PPM")
        (field (name "POWER") "0.1W")
        (field (name "AUTHOR") "CERN DEM JLC")
      )
      (libsource (lib "Resistors") (part "Resistor - 1%"))
    )
    (comp (ref "R112")
      (value "1k1")
      (footprint "RESC1608X55N")
      (description "Resistor - 1%")
      (fields
        (field (name "PART NUMBER") "R0603_1K1_1%_0.1W_100PPM")
        (field (name "POWER") "0.1W")
        (field (name "AUTHOR") "CERN DEM JLC")
      )
      (libsource (lib "Resistors") (part "Resistor - 1%"))
    )
    (comp (ref "R120")
      (value "5k1")
      (footprint "RESC1608X55N")
      (description "Resistor - 1%")
      (fields
        (field (name "PART NUMBER") "R0603_5K1_1%_0.1W_100PPM")
        (field (name "POWER") "0.1W")
        (field (name "AUTHOR") "CERN DEM JLC")
      )
      (libsource (lib "Resistors") (part "Resistor - 1%"))
    )
    (comp (ref "R125")
      (value "7k5")
      (footprint "RESC1608X55N")
      (description "Resistor - 1%")
      (fields
        (field (name "PART NUMBER") "R0603_7K5_1%_0.1W_100PPM")
        (field (name "POWER") "0.1W")
        (field (name "AUTHOR") "CERN DEM JLC")
      )
      (libsource (lib "Resistors") (part "Resistor - 1%"))
    )
    (comp (ref "R128")
      (value "10k")
      (footprint "RESC1608X55N")
      (description "Resistor - 1%")
      (fields
        (field (name "PART NUMBER") "R0603_10K_1%_0.1W_100PPM")
        (field (name "POWER") "0.1W")
        (field (name "AUTHOR") "CERN DEM JLC")
      )
      (libsource (lib "Resistors") (part "Resistor - 1%"))
    )
    (comp (ref "R129")
      (value "10k")
      (footprint "RESC1608X55N")
      (description "Resistor - 1%")
      (fields
        (field (name "PART NUMBER") "R0603_10K_1%_0.1W_100PPM")
        (field (name "POWER") "0.1W")
        (field (name "AUTHOR") "CERN DEM JLC")
      )
      (libsource (lib "Resistors") (part "Resistor - 1%"))
    )
    (comp (ref "R130")
      (value "10k")
      (footprint "RESC1608X55N")
      (description "Resistor - 1%")
      (fields
        (field (name "PART NUMBER") "R0603_10K_1%_0.1W_100PPM")
        (field (name "POWER") "0.1W")
        (field (name "AUTHOR") "CERN DEM JLC")
      )
      (libsource (lib "Resistors") (part "Resistor - 1%"))
    )
    (comp (ref "R134")
      (value "1k1")
      (footprint "RESC1608X55N")
      (description "Resistor - 1%")
      (fields
        (field (name "PART NUMBER") "R0603_1K1_1%_0.1W_100PPM")
        (field (name "POWER") "0.1W")
        (field (name "AUTHOR") "CERN DEM JLC")
      )
      (libsource (lib "Resistors") (part "Resistor - 1%"))
    )
    (comp (ref "R146")
      (value "10k")
      (footprint "RESC1608X55N")
      (description "Resistor - 1%")
      (fields
        (field (name "PART NUMBER") "R0603_10K_1%_0.1W_100PPM")
        (field (name "POWER") "0.1W")
        (field (name "AUTHOR") "CERN DEM JLC")
      )
      (libsource (lib "Resistors") (part "Resistor - 1%"))
    )
    (comp (ref "R147")
      (value "7k5")
      (footprint "RESC1608X55N")
      (description "Resistor - 1%")
      (fields
        (field (name "PART NUMBER") "R0603_7K5_1%_0.1W_100PPM")
        (field (name "POWER") "0.1W")
        (field (name "AUTHOR") "CERN DEM JLC")
      )
      (libsource (lib "Resistors") (part "Resistor - 1%"))
    )
    (comp (ref "R150")
      (value "10k")
      (footprint "RESC1608X55N")
      (description "Resistor - 1%")
      (fields
        (field (name "PART NUMBER") "R0603_10K_1%_0.1W_100PPM")
        (field (name "POWER") "0.1W")
        (field (name "AUTHOR") "CERN DEM JLC")
      )
      (libsource (lib "Resistors") (part "Resistor - 1%"))
    )
    (comp (ref "R153")
      (value "3k3")
      (footprint "RESC1608X55N")
      (description "Resistor - 1%")
      (fields
        (field (name "PART NUMBER") "R0603_3K3_1%_0.1W_100PPM")
        (field (name "POWER") "0.1W")
        (field (name "AUTHOR") "CERN DEM JLC")
      )
      (libsource (lib "Resistors") (part "Resistor - 1%"))
    )
    (comp (ref "R155")
      (value "5k1")
      (footprint "RESC1608X55N")
      (description "Resistor - 1%")
      (fields
        (field (name "PART NUMBER") "R0603_5K1_1%_0.1W_100PPM")
        (field (name "POWER") "0.1W")
        (field (name "AUTHOR") "CERN DEM JLC")
      )
      (libsource (lib "Resistors") (part "Resistor - 1%"))
    )
    (comp (ref "R156")
      (value "7k5")
      (footprint "RESC1608X55N")
      (description "Resistor - 1%")
      (fields
        (field (name "PART NUMBER") "R0603_7K5_1%_0.1W_100PPM")
        (field (name "POWER") "0.1W")
        (field (name "AUTHOR") "CERN DEM JLC")
      )
      (libsource (lib "Resistors") (part "Resistor - 1%"))
    )
    (comp (ref "R167")
      (value "10k")
      (footprint "RESC1608X55N")
      (description "Resistor - 1%")
      (fields
        (field (name "PART NUMBER") "R0603_10K_1%_0.1W_100PPM")
        (field (name "POWER") "0.1W")
        (field (name "AUTHOR") "CERN DEM JLC")
      )
      (libsource (lib "Resistors") (part "Resistor - 1%"))
    )
    (comp (ref "R168")
      (value "10k")
      (footprint "RESC1608X55N")
      (description "Resistor - 1%")
      (fields
        (field (name "PART NUMBER") "R0603_10K_1%_0.1W_100PPM")
        (field (name "POWER") "0.1W")
        (field (name "AUTHOR") "CERN DEM JLC")
      )
      (libsource (lib "Resistors") (part "Resistor - 1%"))
    )
    (comp (ref "R169")
      (value "47k")
      (footprint "RESC1608X55N")
      (description "Resistor - 1%")
      (fields
        (field (name "PART NUMBER") "R0603_47K_1%_0.1W_100PPM")
        (field (name "POWER") "0.1W")
        (field (name "AUTHOR") "CERN DEM JLC")
      )
      (libsource (lib "Resistors") (part "Resistor - 1%"))
    )
    (comp (ref "R170")
      (value "5k1")
      (footprint "RESC1608X55N")
      (description "Resistor - 1%")
      (fields
        (field (name "PART NUMBER") "R0603_5K1_1%_0.1W_100PPM")
        (field (name "POWER") "0.1W")
        (field (name "AUTHOR") "CERN DEM JLC")
      )
      (libsource (lib "Resistors") (part "Resistor - 1%"))
    )
    (comp (ref "R171")
      (value "7k5")
      (footprint "RESC1608X55N")
      (description "Resistor - 1%")
      (fields
        (field (name "PART NUMBER") "R0603_7K5_1%_0.1W_100PPM")
        (field (name "POWER") "0.1W")
        (field (name "AUTHOR") "CERN DEM JLC")
      )
      (libsource (lib "Resistors") (part "Resistor - 1%"))
    )
    (comp (ref "R178")
      (value "470k")
      (footprint "RESC1608X55N")
      (description "Resistor - 1%")
      (fields
        (field (name "PART NUMBER") "R0603_470K_1%_0.1W_100PPM")
        (field (name "POWER") "0.1W")
        (field (name "AUTHOR") "CERN DEM JLC")
      )
      (libsource (lib "Resistors") (part "Resistor - 1%"))
    )
    (comp (ref "R183")
      (value "47k")
      (footprint "RESC1608X55N")
      (description "Resistor - 1%")
      (fields
        (field (name "PART NUMBER") "R0603_47K_1%_0.1W_100PPM")
        (field (name "POWER") "0.1W")
        (field (name "AUTHOR") "CERN DEM JLC")
      )
      (libsource (lib "Resistors") (part "Resistor - 1%"))
    )
    (comp (ref "R184")
      (value "39")
      (footprint "RESC1608X55N")
      (description "Resistor - 1%")
      (fields
        (field (name "PART NUMBER") "R0603_39R_1%_0.1W_100PPM")
        (field (name "POWER") "0.1W")
        (field (name "AUTHOR") "CERN DEM JLC")
      )
      (libsource (lib "Resistors") (part "Resistor - 1%"))
    )
    (comp (ref "R186")
      (value "1k1")
      (footprint "RESC1608X55N")
      (description "Resistor - 1%")
      (fields
        (field (name "PART NUMBER") "R0603_1K1_1%_0.1W_100PPM")
        (field (name "POWER") "0.1W")
        (field (name "AUTHOR") "CERN DEM JLC")
      )
      (libsource (lib "Resistors") (part "Resistor - 1%"))
    )
    (comp (ref "R187")
      (value "10k")
      (footprint "RESC1608X55N")
      (description "Resistor - 1%")
      (fields
        (field (name "PART NUMBER") "R0603_10K_1%_0.1W_100PPM")
        (field (name "POWER") "0.1W")
        (field (name "AUTHOR") "CERN DEM JLC")
      )
      (libsource (lib "Resistors") (part "Resistor - 1%"))
    )
    (comp (ref "R189")
      (value "0R22")
      (footprint "RESC3216X65N")
      (description "Resistor - 1%")
      (fields
        (field (name "PART NUMBER") "R1206_0R22_1%_0.5W_600PPM")
        (field (name "POWER") "0.5W")
        (field (name "AUTHOR") "CERN DEM JMW")
      )
      (libsource (lib "Resistors") (part "Resistor - 1%"))
    )
    (comp (ref "R193")
      (value "0R22")
      (footprint "RESC3216X65N")
      (description "Resistor - 1%")
      (fields
        (field (name "PART NUMBER") "R1206_0R22_1%_0.5W_600PPM")
        (field (name "POWER") "0.5W")
        (field (name "AUTHOR") "CERN DEM JMW")
      )
      (libsource (lib "Resistors") (part "Resistor - 1%"))
    )
    (comp (ref "R194")
      (value "39")
      (footprint "RESC1608X55N")
      (description "Resistor - 1%")
      (fields
        (field (name "PART NUMBER") "R0603_39R_1%_0.1W_100PPM")
        (field (name "POWER") "0.1W")
        (field (name "AUTHOR") "CERN DEM JLC")
      )
      (libsource (lib "Resistors") (part "Resistor - 1%"))
    )
    (comp (ref "T3")
      (value "IRF9910Pbf")
      (footprint "SOIC127P600X175-8N")
      (description "Dual SO-8 MOSFET For POL Cconverter")
      (fields (field (name "MANUFACTURER") "INTERNATIONAL RECTIFIER") (field (name "AUTHOR") "CERN DEM JLC"))
      (libsource (lib "ICs And Semiconductors") (part "IRF9910"))
    )
    (comp (ref "T4")
      (value "IRF9910Pbf")
      (footprint "SOIC127P600X175-8N")
      (description "Dual SO-8 MOSFET For POL Cconverter")
      (fields (field (name "MANUFACTURER") "INTERNATIONAL RECTIFIER") (field (name "AUTHOR") "CERN DEM JLC"))
      (libsource (lib "ICs And Semiconductors") (part "IRF9910"))
    )
    (comp (ref "T7")
      (value "IRF9910Pbf")
      (footprint "SOIC127P600X175-8N")
      (description "Dual SO-8 MOSFET For POL Cconverter")
      (fields (field (name "MANUFACTURER") "INTERNATIONAL RECTIFIER") (field (name "AUTHOR") "CERN DEM JLC"))
      (libsource (lib "ICs And Semiconductors") (part "IRF9910"))
    )
    (comp (ref "T9")
      (value "IRF9910Pbf")
      (footprint "SOIC127P600X175-8N")
      (description "Dual SO-8 MOSFET For POL Cconverter")
      (fields (field (name "MANUFACTURER") "INTERNATIONAL RECTIFIER") (field (name "AUTHOR") "CERN DEM JLC"))
      (libsource (lib "ICs And Semiconductors") (part "IRF9910"))
    )
    (comp (ref "T11")
      (value "BSH103")
      (footprint "SOT95P230X110-3N")
      (description "N-CHANNEL MOSFET WITH DIODE")
      (fields (field (name "MANUFACTURER") "NXP SEMICONDUCTORS") (field (name "AUTHOR") "CERN DEM JLC"))
      (libsource (lib "ICs And Semiconductors") (part "N-MOSFET-D 1G 2S 3D"))
    )
    (comp (ref "T12")
      (value "IRF9910Pbf")
      (footprint "SOIC127P600X175-8N")
      (description "Dual SO-8 MOSFET For POL Cconverter")
      (fields (field (name "MANUFACTURER") "INTERNATIONAL RECTIFIER") (field (name "AUTHOR") "CERN DEM JLC"))
      (libsource (lib "ICs And Semiconductors") (part "IRF9910"))
    )
  )
  (nets
    (net (code "1") (name "/EN_DC_DC") (class "Default")
      (node (ref "IC18") (pin "3") (pinfunction "DIS/~{EN}_3") (pintype "input"))
      (node (ref "IC2") (pin "24") (pinfunction "EN1_24") (pintype "input"))
      (node (ref "IC2") (pin "7") (pinfunction "EN2_7") (pintype "input"))
      (node (ref "IC9") (pin "24") (pinfunction "EN1_24") (pintype "input"))
      (node (ref "IC9") (pin "7") (pinfunction "EN2_7") (pintype "input"))
      (node (ref "R60") (pin "1") (pinfunction "1_1") (pintype "passive"))
    )
    (net (code "2") (name "/Isense") (class "Default")
      (node (ref "R186") (pin "1") (pinfunction "1_1") (pintype "passive"))
      (node (ref "R189") (pin "2") (pinfunction "2_2") (pintype "passive"))
      (node (ref "R193") (pin "2") (pinfunction "2_2") (pintype "passive"))
      (node (ref "T12") (pin "1") (pinfunction "S_1") (pintype "passive"))
      (node (ref "T12") (pin "3") (pinfunction "S_3") (pintype "passive"))
    )
    (net (code "3") (name "/RST_N") (class "Default")
      (node (ref "IC23") (pin "2") (pinfunction "~{RST}_2") (pintype "output"))
    )
    (net (code "4") (name "/SW") (class "Default")
      (node (ref "D1") (pin "1") (pinfunction "A_1") (pintype "passive"))
      (node (ref "D1") (pin "2") (pinfunction "A_2") (pintype "passive"))
      (node (ref "L14") (pin "2") (pinfunction "2_2") (pintype "passive"))
      (node (ref "T12") (pin "5") (pinfunction "D_5") (pintype "passive"))
      (node (ref "T12") (pin "6") (pinfunction "D_6") (pintype "passive"))
      (node (ref "T12") (pin "7") (pinfunction "D_7") (pintype "passive"))
      (node (ref "T12") (pin "8") (pinfunction "D_8") (pintype "passive"))
    )
    (net (code "5") (name "GND") (class "Default")
      (node (ref "B10") (pin "1") (pinfunction "1_1") (pintype "bidirectional"))
      (node (ref "C101") (pin "1") (pinfunction "1_1") (pintype "passive"))
      (node (ref "C102") (pin "1") (pinfunction "1_1") (pintype "passive"))
      (node (ref "C117") (pin "1") (pinfunction "1_1") (pintype "passive"))
      (node (ref "C118") (pin "1") (pinfunction "1_1") (pintype "passive"))
      (node (ref "C119") (pin "1") (pinfunction "1_1") (pintype "passive"))
      (node (ref "C128") (pin "1") (pinfunction "1_1") (pintype "passive"))
      (node (ref "C135") (pin "1") (pinfunction "1_1") (pintype "passive"))
      (node (ref "C136") (pin "1") (pinfunction "1_1") (pintype "passive"))
      (node (ref "C137") (pin "1") (pinfunction "1_1") (pintype "passive"))
      (node (ref "C138") (pin "1") (pinfunction "1_1") (pintype "passive"))
      (node (ref "C139") (pin "1") (pinfunction "1_1") (pintype "passive"))
      (node (ref "C148") (pin "1") (pinfunction "1_1") (pintype "passive"))
      (node (ref "C163") (pin "1") (pinfunction "1_1") (pintype "passive"))
      (node (ref "C169") (pin "1") (pinfunction "1_1") (pintype "passive"))
      (node (ref "C173") (pin "1") (pinfunction "1_1") (pintype "passive"))
      (node (ref "C175") (pin "2") (pinfunction "2_2") (pintype "passive"))
      (node (ref "C176") (pin "2") (pinfunction "2_2") (pintype "passive"))
      (node (ref "C179") (pin "2") (pinfunction "2_2") (pintype "passive"))
      (node (ref "C180") (pin "1") (pinfunction "1_1") (pintype "passive"))
      (node (ref "C181") (pin "1") (pinfunction "1_1") (pintype "passive"))
      (node (ref "C182") (pin "2") (pinfunction "2_2") (pintype "passive"))
      (node (ref "C183") (pin "1") (pinfunction "1_1") (pintype "passive"))
      (node (ref "C209") (pin "1") (pinfunction "1_1") (pintype "passive"))
      (node (ref "C210") (pin "1") (pinfunction "1_1") (pintype "passive"))
      (node (ref "C211") (pin "2") (pinfunction "2_2") (pintype "passive"))
      (node (ref "C212") (pin "1") (pinfunction "1_1") (pintype "passive"))
      (node (ref "C218") (pin "1") (pinfunction "1_1") (pintype "passive"))
      (node (ref "C224") (pin "2") (pinfunction "2_2") (pintype "passive"))
      (node (ref "C225") (pin "2") (pinfunction "2_2") (pintype "passive"))
      (node (ref "C241") (pin "2") (pinfunction "2_2") (pintype "passive"))
      (node (ref "C298") (pin "1") (pinfunction "1_1") (pintype "passive"))
      (node (ref "C299") (pin "1") (pinfunction "1_1") (pintype "passive"))
      (node (ref "C300") (pin "1") (pinfunction "1_1") (pintype "passive"))
      (node (ref "C309") (pin "1") (pinfunction "1_1") (pintype "passive"))
      (node (ref "C31") (pin "1") (pinfunction "1_1") (pintype "passive"))
      (node (ref "C310") (pin "1") (pinfunction "1_1") (pintype "passive"))
      (node (ref "C316") (pin "1") (pinfunction "1_1") (pintype "passive"))
      (node (ref "C321") (pin "1") (pinfunction "1_1") (pintype "passive"))
      (node (ref "C322") (pin "1") (pinfunction "1_1") (pintype "passive"))
      (node (ref "C33") (pin "1") (pinfunction "1_1") (pintype "passive"))
      (node (ref "C35") (pin "1") (pinfunction "1_1") (pintype "passive"))
      (node (ref "C412") (pin "2") (pinfunction "2_2") (pintype "passive"))
      (node (ref "C43") (pin "1") (pinfunction "1_1") (pintype "passive"))
      (node (ref "C435") (pin "2") (pinfunction "2_2") (pintype "passive"))
      (node (ref "C44") (pin "2") (pinfunction "2_2") (pintype "passive"))
      (node (ref "C45") (pin "1") (pinfunction "1_1") (pintype "passive"))
      (node (ref "C46") (pin "1") (pinfunction "1_1") (pintype "passive"))
      (node (ref "C47") (pin "1") (pinfunction "1_1") (pintype "passive"))
      (node (ref "C49") (pin "1") (pinfunction "1_1") (pintype "passive"))
      (node (ref "C5") (pin "1") (pinfunction "1_1") (pintype "passive"))
      (node (ref "C60") (pin "2") (pinfunction "2_2") (pintype "passive"))
      (node (ref "C61") (pin "1") (pinfunction "1_1") (pintype "passive"))
      (node (ref "C62") (pin "1") (pinfunction "1_1") (pintype "passive"))
      (node (ref "C66") (pin "1") (pinfunction "1_1") (pintype "passive"))
      (node (ref "C67") (pin "1") (pinfunction "1_1") (pintype "passive"))
      (node (ref "C68") (pin "1") (pinfunction "1_1") (pintype "passive"))
      (node (ref "C71") (pin "1") (pinfunction "1_1") (pintype "passive"))
      (node (ref "C72") (pin "1") (pinfunction "1_1") (pintype "passive"))
      (node (ref "C77") (pin "1") (pinfunction "1_1") (pintype "passive"))
      (node (ref "C90") (pin "1") (pinfunction "1_1") (pintype "passive"))
      (node (ref "C91") (pin "1") (pinfunction "1_1") (pintype "passive"))
      (node (ref "C93") (pin "1") (pinfunction "1_1") (pintype "passive"))
      (node (ref "IC18") (pin "11") (pinfunction "EP_11") (pintype "power_in"))
      (node (ref "IC18") (pin "6") (pinfunction "GND_6") (pintype "power_in"))
      (node (ref "IC2") (pin "12") (pinfunction "PGND2_12") (pintype "power_in"))
      (node (ref "IC2") (pin "14") (pinfunction "TEST2_14") (pintype "input"))
      (node (ref "IC2") (pin "19") (pinfunction "PGND1_19") (pintype "power_in"))
      (node (ref "IC2") (pin "25") (pinfunction "EP_25") (pintype "power_in"))
      (node (ref "IC2") (pin "3") (pinfunction "GND_3") (pintype "power_in"))
      (node (ref "IC2") (pin "4") (pinfunction "TEST1_4") (pintype "output"))
      (node (ref "IC23") (pin "1") (pinfunction "VSS_1") (pintype "power_in"))
      (node (ref "IC8") (pin "11") (pinfunction "EP_11") (pintype "power_in"))
      (node (ref "IC8") (pin "4") (pinfunction "PGND_4") (pintype "power_in"))
      (node (ref "IC8") (pin "8") (pinfunction "GND_8") (pintype "power_in"))
      (node (ref "IC9") (pin "12") (pinfunction "PGND2_12") (pintype "power_in"))
      (node (ref "IC9") (pin "14") (pinfunction "TEST2_14") (pintype "input"))
      (node (ref "IC9") (pin "19") (pinfunction "PGND1_19") (pintype "power_in"))
      (node (ref "IC9") (pin "25") (pinfunction "EP_25") (pintype "power_in"))
      (node (ref "IC9") (pin "3") (pinfunction "GND_3") (pintype "power_in"))
      (node (ref "IC9") (pin "4") (pinfunction "TEST1_4") (pintype "output"))
      (node (ref "LD15") (pin "1") (pinfunction "C_1") (pintype "passive"))
      (node (ref "R11") (pin "1") (pinfunction "1_1") (pintype "passive"))
      (node (ref "R12") (pin "1") (pinfunction "1_1") (pintype "passive"))
      (node (ref "R120") (pin "1") (pinfunction "1_1") (pintype "passive"))
      (node (ref "R128") (pin "1") (pinfunction "1_1") (pintype "passive"))
      (node (ref "R146") (pin "2") (pinfunction "2_2") (pintype "passive"))
      (node (ref "R153") (pin "2") (pinfunction "2_2") (pintype "passive"))
      (node (ref "R155") (pin "1") (pinfunction "1_1") (pintype "passive"))
      (node (ref "R156") (pin "2") (pinfunction "2_2") (pintype "passive"))
      (node (ref "R170") (pin "1") (pinfunction "1_1") (pintype "passive"))
      (node (ref "R171") (pin "1") (pinfunction "1_1") (pintype "passive"))
      (node (ref "R189") (pin "1") (pinfunction "1_1") (pintype "passive"))
      (node (ref "R193") (pin "1") (pinfunction "1_1") (pintype "passive"))
      (node (ref "R22") (pin "1") (pinfunction "1_1") (pintype "passive"))
      (node (ref "T11") (pin "2") (pinfunction "S_2") (pintype "passive"))
      (node (ref "T3") (pin "1") (pinfunction "S_1") (pintype "passive"))
      (node (ref "T4") (pin "1") (pinfunction "S_1") (pintype "passive"))
      (node (ref "T7") (pin "1") (pinfunction "S_1") (pintype "passive"))
      (node (ref "T9") (pin "1") (pinfunction "S_1") (pintype "passive"))
    )
    (net (code "6") (name "Net-(C78-Pad2)") (class "Default")
      (node (ref "C78") (pin "2") (pinfunction "2_2") (pintype "passive"))
      (node (ref "R130") (pin "1") (pinfunction "1_1") (pintype "passive"))
    )
    (net (code "7") (name "Net-(IC2-DRVH1)") (class "Default")
      (node (ref "IC2") (pin "22") (pinfunction "DRVH1_22") (pintype "output"))
      (node (ref "T7") (pin "4") (pinfunction "G_4") (pintype "passive"))
    )
    (net (code "8") (name "Net-(IC2-DRVH2)") (class "Default")
      (node (ref "IC2") (pin "9") (pinfunction "DRVH2_9") (pintype "output"))
      (node (ref "T9") (pin "4") (pinfunction "G_4") (pintype "passive"))
    )
    (net (code "9") (name "Net-(IC2-DRVL1)") (class "Default")
      (node (ref "IC2") (pin "20") (pinfunction "DRVL1_20") (pintype "output"))
      (node (ref "T7") (pin "2") (pinfunction "G_2") (pintype "passive"))
    )
    (net (code "10") (name "Net-(IC2-DRVL2)") (class "Default")
      (node (ref "IC2") (pin "11") (pinfunction "DRVL2_11") (pintype "output"))
      (node (ref "T9") (pin "2") (pinfunction "G_2") (pintype "passive"))
    )
    (net (code "11") (name "Net-(IC2-SW1)") (class "Default")
      (node (ref "C167") (pin "2") (pinfunction "2_2") (pintype "passive"))
      (node (ref "IC2") (pin "21") (pinfunction "SW1_21") (pintype "bidirectional"))
      (node (ref "L12") (pin "1") (pinfunction "1_1") (pintype "passive"))
      (node (ref "T7") (pin "3") (pinfunction "S_3") (pintype "passive"))
      (node (ref "T7") (pin "7") (pinfunction "D_7") (pintype "passive"))
      (node (ref "T7") (pin "8") (pinfunction "D_8") (pintype "passive"))
    )
    (net (code "12") (name "Net-(IC2-SW2)") (class "Default")
      (node (ref "C195") (pin "2") (pinfunction "2_2") (pintype "passive"))
      (node (ref "IC2") (pin "10") (pinfunction "SW2_10") (pintype "bidirectional"))
      (node (ref "L13") (pin "1") (pinfunction "1_1") (pintype "passive"))
      (node (ref "T9") (pin "3") (pinfunction "S_3") (pintype "passive"))
      (node (ref "T9") (pin "7") (pinfunction "D_7") (pintype "passive"))
      (node (ref "T9") (pin "8") (pinfunction "D_8") (pintype "passive"))
    )
    (net (code "13") (name "Net-(IC2-TRIP1)") (class "Default")
      (node (ref "IC2") (pin "18") (pinfunction "TRIP1_18") (pintype "input"))
      (node (ref "R12") (pin "2") (pinfunction "2_2") (pintype "passive"))
    )
    (net (code "14") (name "Net-(IC2-TRIP2)") (class "Default")
      (node (ref "IC2") (pin "13") (pinfunction "TRIP2_13") (pintype "input"))
      (node (ref "R155") (pin "2") (pinfunction "2_2") (pintype "passive"))
    )
    (net (code "15") (name "Net-(IC2-V5FILT)") (class "Default")
      (node (ref "C300") (pin "2") (pinfunction "2_2") (pintype "passive"))
      (node (ref "IC2") (pin "15") (pinfunction "V5FILT_15") (pintype "input"))
    )
    (net (code "16") (name "Net-(IC2-VBST1)") (class "Default")
      (node (ref "C167") (pin "1") (pinfunction "1_1") (pintype "passive"))
      (node (ref "IC2") (pin "23") (pinfunction "VBST1_23") (pintype "input"))
    )
    (net (code "17") (name "Net-(IC2-VBST2)") (class "Default")
      (node (ref "C195") (pin "1") (pinfunction "1_1") (pintype "passive"))
      (node (ref "IC2") (pin "8") (pinfunction "VBST2_8") (pintype "input"))
    )
    (net (code "18") (name "Net-(IC2-VFB1)") (class "Default")
      (node (ref "IC2") (pin "2") (pinfunction "VFB1_2") (pintype "input"))
      (node (ref "R128") (pin "2") (pinfunction "2_2") (pintype "passive"))
      (node (ref "R168") (pin "1") (pinfunction "1_1") (pintype "passive"))
    )
    (net (code "19") (name "Net-(IC2-VFB2)") (class "Default")
      (node (ref "IC2") (pin "5") (pinfunction "VFB2_5") (pintype "input"))
      (node (ref "R129") (pin "1") (pinfunction "1_1") (pintype "passive"))
      (node (ref "R156") (pin "1") (pinfunction "1_1") (pintype "passive"))
      (node (ref "R26") (pin "2") (pinfunction "2_2") (pintype "passive"))
    )
    (net (code "20") (name "Net-(IC2-VREG5)") (class "Default")
      (node (ref "C35") (pin "2") (pinfunction "2_2") (pintype "passive"))
      (node (ref "IC2") (pin "16") (pinfunction "VREG5_16") (pintype "output"))
    )
    (net (code "21") (name "Net-(IC8-PGOOD)") (class "Default")
      (node (ref "IC8") (pin "9") (pinfunction "PGOOD_9") (pintype "output"))
      (node (ref "R150") (pin "1") (pinfunction "1_1") (pintype "passive"))
      (node (ref "T11") (pin "1") (pinfunction "G_1") (pintype "passive"))
    )
    (net (code "22") (name "Net-(IC8-REFIN)") (class "Default")
      (node (ref "C43") (pin "2") (pinfunction "2_2") (pintype "passive"))
      (node (ref "IC8") (pin "1") (pinfunction "REFIN_1") (pintype "input"))
      (node (ref "R146") (pin "1") (pinfunction "1_1") (pintype "passive"))
      (node (ref "R187") (pin "1") (pinfunction "1_1") (pintype "passive"))
    )
    (net (code "23") (name "Net-(IC9-DRVH1)") (class "Default")
      (node (ref "IC9") (pin "22") (pinfunction "DRVH1_22") (pintype "output"))
      (node (ref "T3") (pin "4") (pinfunction "G_4") (pintype "passive"))
    )
    (net (code "24") (name "Net-(IC9-DRVH2)") (class "Default")
      (node (ref "IC9") (pin "9") (pinfunction "DRVH2_9") (pintype "output"))
      (node (ref "T4") (pin "4") (pinfunction "G_4") (pintype "passive"))
    )
    (net (code "25") (name "Net-(IC9-DRVL1)") (class "Default")
      (node (ref "IC9") (pin "20") (pinfunction "DRVL1_20") (pintype "output"))
      (node (ref "T3") (pin "2") (pinfunction "G_2") (pintype "passive"))
    )
    (net (code "26") (name "Net-(IC9-DRVL2)") (class "Default")
      (node (ref "IC9") (pin "11") (pinfunction "DRVL2_11") (pintype "output"))
      (node (ref "T4") (pin "2") (pinfunction "G_2") (pintype "passive"))
    )
    (net (code "27") (name "Net-(IC9-SW1)") (class "Default")
      (node (ref "C38") (pin "2") (pinfunction "2_2") (pintype "passive"))
      (node (ref "IC9") (pin "21") (pinfunction "SW1_21") (pintype "bidirectional"))
      (node (ref "L3") (pin "1") (pinfunction "1_1") (pintype "passive"))
      (node (ref "T3") (pin "3") (pinfunction "S_3") (pintype "passive"))
      (node (ref "T3") (pin "7") (pinfunction "D_7") (pintype "passive"))
      (node (ref "T3") (pin "8") (pinfunction "D_8") (pintype "passive"))
    )
    (net (code "28") (name "Net-(IC9-SW2)") (class "Default")
      (node (ref "C39") (pin "2") (pinfunction "2_2") (pintype "passive"))
      (node (ref "IC9") (pin "10") (pinfunction "SW2_10") (pintype "bidirectional"))
      (node (ref "L4") (pin "1") (pinfunction "1_1") (pintype "passive"))
      (node (ref "T4") (pin "3") (pinfunction "S_3") (pintype "passive"))
      (node (ref "T4") (pin "7") (pinfunction "D_7") (pintype "passive"))
      (node (ref "T4") (pin "8") (pinfunction "D_8") (pintype "passive"))
    )
    (net (code "29") (name "Net-(IC9-TRIP1)") (class "Default")
      (node (ref "IC9") (pin "18") (pinfunction "TRIP1_18") (pintype "input"))
      (node (ref "R120") (pin "2") (pinfunction "2_2") (pintype "passive"))
    )
    (net (code "30") (name "Net-(IC9-TRIP2)") (class "Default")
      (node (ref "IC9") (pin "13") (pinfunction "TRIP2_13") (pintype "input"))
      (node (ref "R11") (pin "2") (pinfunction "2_2") (pintype "passive"))
    )
    (net (code "31") (name "Net-(IC9-V5FILT)") (class "Default")
      (node (ref "C5") (pin "2") (pinfunction "2_2") (pintype "passive"))
      (node (ref "IC9") (pin "15") (pinfunction "V5FILT_15") (pintype "input"))
    )
    (net (code "32") (name "Net-(IC9-VBST1)") (class "Default")
      (node (ref "C38") (pin "1") (pinfunction "1_1") (pintype "passive"))
      (node (ref "IC9") (pin "23") (pinfunction "VBST1_23") (pintype "input"))
    )
    (net (code "33") (name "Net-(IC9-VBST2)") (class "Default")
      (node (ref "C39") (pin "1") (pinfunction "1_1") (pintype "passive"))
      (node (ref "IC9") (pin "8") (pinfunction "VBST2_8") (pintype "input"))
    )
    (net (code "34") (name "Net-(IC9-VFB1)") (class "Default")
      (node (ref "IC9") (pin "2") (pinfunction "VFB1_2") (pintype "input"))
      (node (ref "R147") (pin "1") (pinfunction "1_1") (pintype "passive"))
      (node (ref "R22") (pin "2") (pinfunction "2_2") (pintype "passive"))
    )
    (net (code "35") (name "Net-(IC9-VFB2)") (class "Default")
      (node (ref "IC9") (pin "5") (pinfunction "VFB2_5") (pintype "input"))
      (node (ref "R125") (pin "2") (pinfunction "2_2") (pintype "passive"))
      (node (ref "R153") (pin "1") (pinfunction "1_1") (pintype "passive"))
    )
    (net (code "36") (name "Net-(IC9-VREG5)") (class "Default")
      (node (ref "C173") (pin "2") (pinfunction "2_2") (pintype "passive"))
      (node (ref "IC9") (pin "16") (pinfunction "VREG5_16") (pintype "output"))
    )
    (net (code "37") (name "Net-(IC18-BP)") (class "Default")
      (node (ref "C33") (pin "2") (pinfunction "2_2") (pintype "passive"))
      (node (ref "IC18") (pin "9") (pinfunction "BP_9") (pintype "output"))
    )
    (net (code "38") (name "Net-(IC18-COMP)") (class "Default")
      (node (ref "C100") (pin "2") (pinfunction "2_2") (pintype "passive"))
      (node (ref "C116") (pin "2") (pinfunction "2_2") (pintype "passive"))
      (node (ref "C79") (pin "2") (pinfunction "2_2") (pintype "passive"))
      (node (ref "IC18") (pin "4") (pinfunction "COMP_4") (pintype "output"))
      (node (ref "R169") (pin "2") (pinfunction "2_2") (pintype "passive"))
    )
    (net (code "39") (name "Net-(IC18-FB)") (class "Default")
      (node (ref "C100") (pin "1") (pinfunction "1_1") (pintype "passive"))
      (node (ref "C116") (pin "1") (pinfunction "1_1") (pintype "passive"))
      (node (ref "C78") (pin "1") (pinfunction "1_1") (pintype "passive"))
      (node (ref "C79") (pin "1") (pinfunction "1_1") (pintype "passive"))
      (node (ref "IC18") (pin "5") (pinfunction "FB_5") (pintype "input"))
      (node (ref "R170") (pin "2") (pinfunction "2_2") (pintype "passive"))
      (node (ref "R171") (pin "2") (pinfunction "2_2") (pintype "passive"))
      (node (ref "R183") (pin "1") (pinfunction "1_1") (pintype "passive"))
    )
    (net (code "40") (name "Net-(IC18-GDRV)") (class "Default")
      (node (ref "IC18") (pin "8") (pinfunction "GDRV_8") (pintype "output"))
      (node (ref "R184") (pin "2") (pinfunction "2_2") (pintype "passive"))
      (node (ref "R194") (pin "1") (pinfunction "1_1") (pintype "passive"))
    )
    (net (code "41") (name "Net-(IC18-ISNS)") (class "Default")
      (node (ref "C298") (pin "2") (pinfunction "2_2") (pintype "passive"))
      (node (ref "C299") (pin "2") (pinfunction "2_2") (pintype "passive"))
      (node (ref "IC18") (pin "7") (pinfunction "ISNS_7") (pintype "input"))
      (node (ref "R186") (pin "2") (pinfunction "2_2") (pintype "passive"))
    )
    (net (code "42") (name "Net-(IC18-RC)") (class "Default")
      (node (ref "C101") (pin "2") (pinfunction "2_2") (pintype "passive"))
      (node (ref "IC18") (pin "1") (pinfunction "RC_1") (pintype "input"))
      (node (ref "R178") (pin "1") (pinfunction "1_1") (pintype "passive"))
    )
    (net (code "43") (name "Net-(IC18-SS)") (class "Default")
      (node (ref "C102") (pin "2") (pinfunction "2_2") (pintype "passive"))
      (node (ref "IC18") (pin "2") (pinfunction "SS_2") (pintype "input"))
    )
    (net (code "44") (name "Net-(LD15-A)") (class "Default")
      (node (ref "LD15") (pin "2") (pinfunction "A_2") (pintype "passive"))
      (node (ref "R112") (pin "1") (pinfunction "1_1") (pintype "passive"))
    )
    (net (code "45") (name "Net-(LD19-A)") (class "Default")
      (node (ref "LD19") (pin "2") (pinfunction "A_2") (pintype "passive"))
      (node (ref "R134") (pin "1") (pinfunction "1_1") (pintype "passive"))
    )
    (net (code "46") (name "Net-(LD19-C)") (class "Default")
      (node (ref "LD19") (pin "1") (pinfunction "C_1") (pintype "passive"))
      (node (ref "T11") (pin "3") (pinfunction "D_3") (pintype "passive"))
    )
    (net (code "47") (name "Net-(R130-Pad2)") (class "Default")
      (node (ref "R130") (pin "2") (pinfunction "2_2") (pintype "passive"))
      (node (ref "R167") (pin "2") (pinfunction "2_2") (pintype "passive"))
    )
    (net (code "48") (name "Net-(R167-Pad1)") (class "Default")
      (node (ref "R167") (pin "1") (pinfunction "1_1") (pintype "passive"))
      (node (ref "R169") (pin "1") (pinfunction "1_1") (pintype "passive"))
    )
    (net (code "49") (name "Net-(T12A-G)") (class "Default")
      (node (ref "R184") (pin "1") (pinfunction "1_1") (pintype "passive"))
      (node (ref "T12") (pin "4") (pinfunction "G_4") (pintype "passive"))
    )
    (net (code "50") (name "Net-(T12B-G)") (class "Default")
      (node (ref "R194") (pin "2") (pinfunction "2_2") (pintype "passive"))
      (node (ref "T12") (pin "2") (pinfunction "G_2") (pintype "passive"))
    )
    (net (code "51") (name "P1V2") (class "Default")
      (node (ref "B6") (pin "1") (pinfunction "1_1") (pintype "bidirectional"))
      (node (ref "C169") (pin "2") (pinfunction "2_2") (pintype "passive"))
      (node (ref "C181") (pin "2") (pinfunction "2_2") (pintype "passive"))
      (node (ref "C183") (pin "2") (pinfunction "2_2") (pintype "passive"))
      (node (ref "C209") (pin "2") (pinfunction "2_2") (pintype "passive"))
      (node (ref "C210") (pin "2") (pinfunction "2_2") (pintype "passive"))
      (node (ref "C212") (pin "2") (pinfunction "2_2") (pintype "passive"))
      (node (ref "C224") (pin "1") (pinfunction "1_1") (pintype "passive"))
      (node (ref "C225") (pin "1") (pinfunction "1_1") (pintype "passive"))
      (node (ref "C45") (pin "2") (pinfunction "2_2") (pintype "passive"))
      (node (ref "C46") (pin "2") (pinfunction "2_2") (pintype "passive"))
      (node (ref "C47") (pin "2") (pinfunction "2_2") (pintype "passive"))
      (node (ref "C49") (pin "2") (pinfunction "2_2") (pintype "passive"))
      (node (ref "IC2") (pin "6") (pinfunction "VO2_6") (pintype "input"))
      (node (ref "L13") (pin "2") (pinfunction "2_2") (pintype "passive"))
      (node (ref "R129") (pin "2") (pinfunction "2_2") (pintype "passive"))
      (node (ref "R26") (pin "1") (pinfunction "1_1") (pintype "passive"))
    )
    (net (code "52") (name "P1V5") (class "Default")
      (node (ref "C163") (pin "2") (pinfunction "2_2") (pintype "passive"))
      (node (ref "C182") (pin "1") (pinfunction "1_1") (pintype "passive"))
      (node (ref "C66") (pin "2") (pinfunction "2_2") (pintype "passive"))
      (node (ref "C90") (pin "2") (pinfunction "2_2") (pintype "passive"))
      (node (ref "C93") (pin "2") (pinfunction "2_2") (pintype "passive"))
      (node (ref "IC2") (pin "1") (pinfunction "VO1_1") (pintype "input"))
      (node (ref "IC8") (pin "2") (pinfunction "VLDOIN_2") (pintype "input"))
      (node (ref "L12") (pin "2") (pinfunction "2_2") (pintype "passive"))
      (node (ref "R168") (pin "2") (pinfunction "2_2") (pintype "passive"))
      (node (ref "R187") (pin "2") (pinfunction "2_2") (pintype "passive"))
    )
    (net (code "53") (name "P1V8") (class "Default")
      (node (ref "B2") (pin "1") (pinfunction "1_1") (pintype "bidirectional"))
    )
    (net (code "54") (name "P2V5") (class "Default")
      (node (ref "B9") (pin "1") (pinfunction "1_1") (pintype "bidirectional"))
      (node (ref "C128") (pin "2") (pinfunction "2_2") (pintype "passive"))
      (node (ref "C139") (pin "2") (pinfunction "2_2") (pintype "passive"))
      (node (ref "C148") (pin "2") (pinfunction "2_2") (pintype "passive"))
      (node (ref "C60") (pin "1") (pinfunction "1_1") (pintype "passive"))
      (node (ref "C72") (pin "2") (pinfunction "2_2") (pintype "passive"))
      (node (ref "C77") (pin "2") (pinfunction "2_2") (pintype "passive"))
      (node (ref "IC9") (pin "6") (pinfunction "VO2_6") (pintype "input"))
      (node (ref "L4") (pin "2") (pinfunction "2_2") (pintype "passive"))
      (node (ref "R125") (pin "1") (pinfunction "1_1") (pintype "passive"))
    )
    (net (code "55") (name "P2V5_FMC") (class "Default")
      (node (ref "C119") (pin "2") (pinfunction "2_2") (pintype "passive"))
      (node (ref "C135") (pin "2") (pinfunction "2_2") (pintype "passive"))
      (node (ref "C136") (pin "2") (pinfunction "2_2") (pintype "passive"))
      (node (ref "C137") (pin "2") (pinfunction "2_2") (pintype "passive"))
      (node (ref "C138") (pin "2") (pinfunction "2_2") (pintype "passive"))
      (node (ref "C176") (pin "1") (pinfunction "1_1") (pintype "passive"))
      (node (ref "C179") (pin "1") (pinfunction "1_1") (pintype "passive"))
      (node (ref "IC9") (pin "1") (pinfunction "VO1_1") (pintype "input"))
      (node (ref "L3") (pin "2") (pinfunction "2_2") (pintype "passive"))
      (node (ref "R147") (pin "2") (pinfunction "2_2") (pintype "passive"))
    )
    (net (code "56") (name "P3V3") (class "Default")
      (node (ref "B8") (pin "1") (pinfunction "1_1") (pintype "bidirectional"))
      (node (ref "C61") (pin "2") (pinfunction "2_2") (pintype "passive"))
      (node (ref "F3") (pin "1") (pinfunction "1_1") (pintype "passive"))
      (node (ref "F4") (pin "1") (pinfunction "1_1") (pintype "passive"))
      (node (ref "IC23") (pin "3") (pinfunction "VDD_3") (pintype "power_in"))
      (node (ref "IC8") (pin "10") (pinfunction "VIN_10") (pintype "power_in"))
      (node (ref "IC8") (pin "7") (pinfunction "EN_7") (pintype "input"))
      (node (ref "R112") (pin "2") (pinfunction "2_2") (pintype "passive"))
      (node (ref "R134") (pin "2") (pinfunction "2_2") (pintype "passive"))
      (node (ref "R150") (pin "2") (pinfunction "2_2") (pintype "passive"))
    )
    (net (code "57") (name "P3V3_FMC1") (class "Default")
      (node (ref "F3") (pin "2") (pinfunction "2_2") (pintype "passive"))
    )
    (net (code "58") (name "P3V3_FMC2") (class "Default")
      (node (ref "F4") (pin "2") (pinfunction "2_2") (pintype "passive"))
    )
    (net (code "59") (name "P5V_VME") (class "Default")
      (node (ref "B1") (pin "1") (pinfunction "1_1") (pintype "bidirectional"))
      (node (ref "C117") (pin "2") (pinfunction "2_2") (pintype "passive"))
      (node (ref "C118") (pin "2") (pinfunction "2_2") (pintype "passive"))
      (node (ref "C211") (pin "1") (pinfunction "1_1") (pintype "passive"))
      (node (ref "C218") (pin "2") (pinfunction "2_2") (pintype "passive"))
      (node (ref "C309") (pin "2") (pinfunction "2_2") (pintype "passive"))
      (node (ref "C31") (pin "2") (pinfunction "2_2") (pintype "passive"))
      (node (ref "C310") (pin "2") (pinfunction "2_2") (pintype "passive"))
      (node (ref "C316") (pin "2") (pinfunction "2_2") (pintype "passive"))
      (node (ref "C321") (pin "2") (pinfunction "2_2") (pintype "passive"))
      (node (ref "C322") (pin "2") (pinfunction "2_2") (pintype "passive"))
      (node (ref "C44") (pin "1") (pinfunction "1_1") (pintype "passive"))
      (node (ref "C67") (pin "2") (pinfunction "2_2") (pintype "passive"))
      (node (ref "C71") (pin "2") (pinfunction "2_2") (pintype "passive"))
      (node (ref "C91") (pin "2") (pinfunction "2_2") (pintype "passive"))
      (node (ref "IC18") (pin "10") (pinfunction "VDD_10") (pintype "open_collector"))
      (node (ref "IC2") (pin "17") (pinfunction "VIN_17") (pintype "input"))
      (node (ref "IC9") (pin "17") (pinfunction "VIN_17") (pintype "input"))
      (node (ref "L14") (pin "1") (pinfunction "1_1") (pintype "passive"))
      (node (ref "R178") (pin "2") (pinfunction "2_2") (pintype "passive"))
      (node (ref "R60") (pin "2") (pinfunction "2_2") (pintype "passive"))
      (node (ref "T3") (pin "5") (pinfunction "D_5") (pintype "passive"))
      (node (ref "T3") (pin "6") (pinfunction "D_6") (pintype "passive"))
      (node (ref "T4") (pin "5") (pinfunction "D_5") (pintype "passive"))
      (node (ref "T4") (pin "6") (pinfunction "D_6") (pintype "passive"))
      (node (ref "T7") (pin "5") (pinfunction "D_5") (pintype "passive"))
      (node (ref "T7") (pin "6") (pinfunction "D_6") (pintype "passive"))
      (node (ref "T9") (pin "5") (pinfunction "D_5") (pintype "passive"))
      (node (ref "T9") (pin "6") (pinfunction "D_6") (pintype "passive"))
    )
    (net (code "60") (name "P12V") (class "Default")
      (node (ref "B5") (pin "1") (pinfunction "1_1") (pintype "bidirectional"))
      (node (ref "C175") (pin "1") (pinfunction "1_1") (pintype "passive"))
      (node (ref "C435") (pin "1") (pinfunction "1_1") (pintype "passive"))
      (node (ref "D1") (pin "3") (pinfunction "C_3") (pintype "passive"))
      (node (ref "F1") (pin "1") (pinfunction "1_1") (pintype "passive"))
      (node (ref "R183") (pin "2") (pinfunction "2_2") (pintype "passive"))
    )
    (net (code "61") (name "P12V_FMC") (class "Default")
      (node (ref "C241") (pin "1") (pinfunction "1_1") (pintype "passive"))
      (node (ref "C412") (pin "1") (pinfunction "1_1") (pintype "passive"))
      (node (ref "F1") (pin "2") (pinfunction "2_2") (pintype "passive"))
    )
    (net (code "62") (name "VREF_DDR3") (class "Default")
      (node (ref "C68") (pin "2") (pinfunction "2_2") (pintype "passive"))
      (node (ref "IC8") (pin "6") (pinfunction "REFOUT_6") (pintype "output"))
    )
    (net (code "63") (name "VTT_DDR3") (class "Default")
      (node (ref "C180") (pin "2") (pinfunction "2_2") (pintype "passive"))
      (node (ref "C62") (pin "2") (pinfunction "2_2") (pintype "passive"))
      (node (ref "IC8") (pin "3") (pinfunction "VO_3") (pintype "power_in"))
      (node (ref "IC8") (pin "5") (pinfunction "VOSNS_5") (pintype "input"))
    )
  )
)
